# LC_LPF_PI.net
KiCad netlist of a schematic drawn in Altium Designer
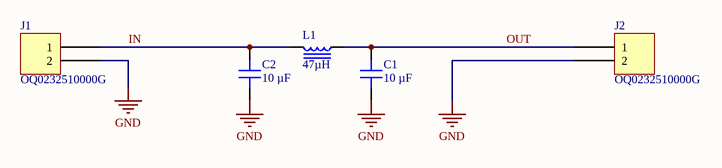
[diagram p0: LC_LPF_PI.SchDoc]

(export (version "E")
  (design (tool "Eeschema 10.0.6"))
  (components
    (comp (ref "C1")
      (value "10 µF")
      (footprint "CAP 0603_1608")
      (description "CAP CER 10UF 10V X5R 0603")
      (fields
        (field (name "PART NUMBER") "MD0603BW106M100NHT-EM")
        (field (name "MANUFACTURER") "Knowles Novacap")
      )
      (libsource (lib "Celestial Altium Library - altium_library") (part "Capacitor"))
    )
    (comp (ref "C2")
      (value "10 µF")
      (footprint "CAP 0603_1608")
      (description "CAP CER 10UF 10V X5R 0603")
      (fields
        (field (name "PART NUMBER") "MD0603BW106M100NHT-EM")
        (field (name "MANUFACTURER") "Knowles Novacap")
      )
      (libsource (lib "Celestial Altium Library - altium_library") (part "Capacitor"))
    )
    (comp (ref "J1")
      (value "OQ0232510000G")
      (footprint "FCI 06-381-2PIN")
      (description "TERM BLOCK HDR 2POS 90DEG 3.81MM")
      (fields (field (name "MANUFACTURER") "Amphenol Anytek"))
      (libsource (lib "Celestial Altium Library - altium_library") (part "2 Pin"))
    )
    (comp (ref "J2")
      (value "OQ0232510000G")
      (footprint "FCI 06-381-2PIN")
      (description "TERM BLOCK HDR 2POS 90DEG 3.81MM")
      (fields (field (name "MANUFACTURER") "Amphenol Anytek"))
      (libsource (lib "") (part "2 Pin_1"))
    )
    (comp (ref "L1")
      (value "47µH")
      (footprint "IND 0603_1608 RF WW")
      (description "INDUCTORPOWER LINE 0603 47H 20%")
      (fields (field (name "PART NUMBER") "L0603B470MPWFT") (field (name "MANUFACTURER") "KEMET"))
      (libsource (lib "Celestial Altium Library - altium_library") (part "Inductor"))
    )
  )
  (nets
    (net (code "1") (name "/IN") (class "Default")
      (node (ref "C2") (pin "2") (pinfunction "2_2") (pintype "passive"))
      (node (ref "J1") (pin "1") (pinfunction "1_1") (pintype "passive"))
      (node (ref "L1") (pin "2") (pinfunction "2_2") (pintype "passive"))
    )
    (net (code "2") (name "/OUT") (class "Default")
      (node (ref "C1") (pin "2") (pinfunction "2_2") (pintype "passive"))
      (node (ref "J2") (pin "1") (pinfunction "1_1") (pintype "passive"))
      (node (ref "L1") (pin "1") (pinfunction "1_1") (pintype "passive"))
    )
    (net (code "3") (name "GND") (class "Default")
      (node (ref "C1") (pin "1") (pinfunction "1_1") (pintype "passive"))
      (node (ref "C2") (pin "1") (pinfunction "1_1") (pintype "passive"))
      (node (ref "J1") (pin "2") (pinfunction "2_2") (pintype "passive"))
      (node (ref "J2") (pin "2") (pinfunction "2_2") (pintype "passive"))
    )
  )
)
